# SCH_SIT210_Task_7_3D_PCB_2022-06-06.net
KiCad netlist of a schematic drawn in EasyEDA
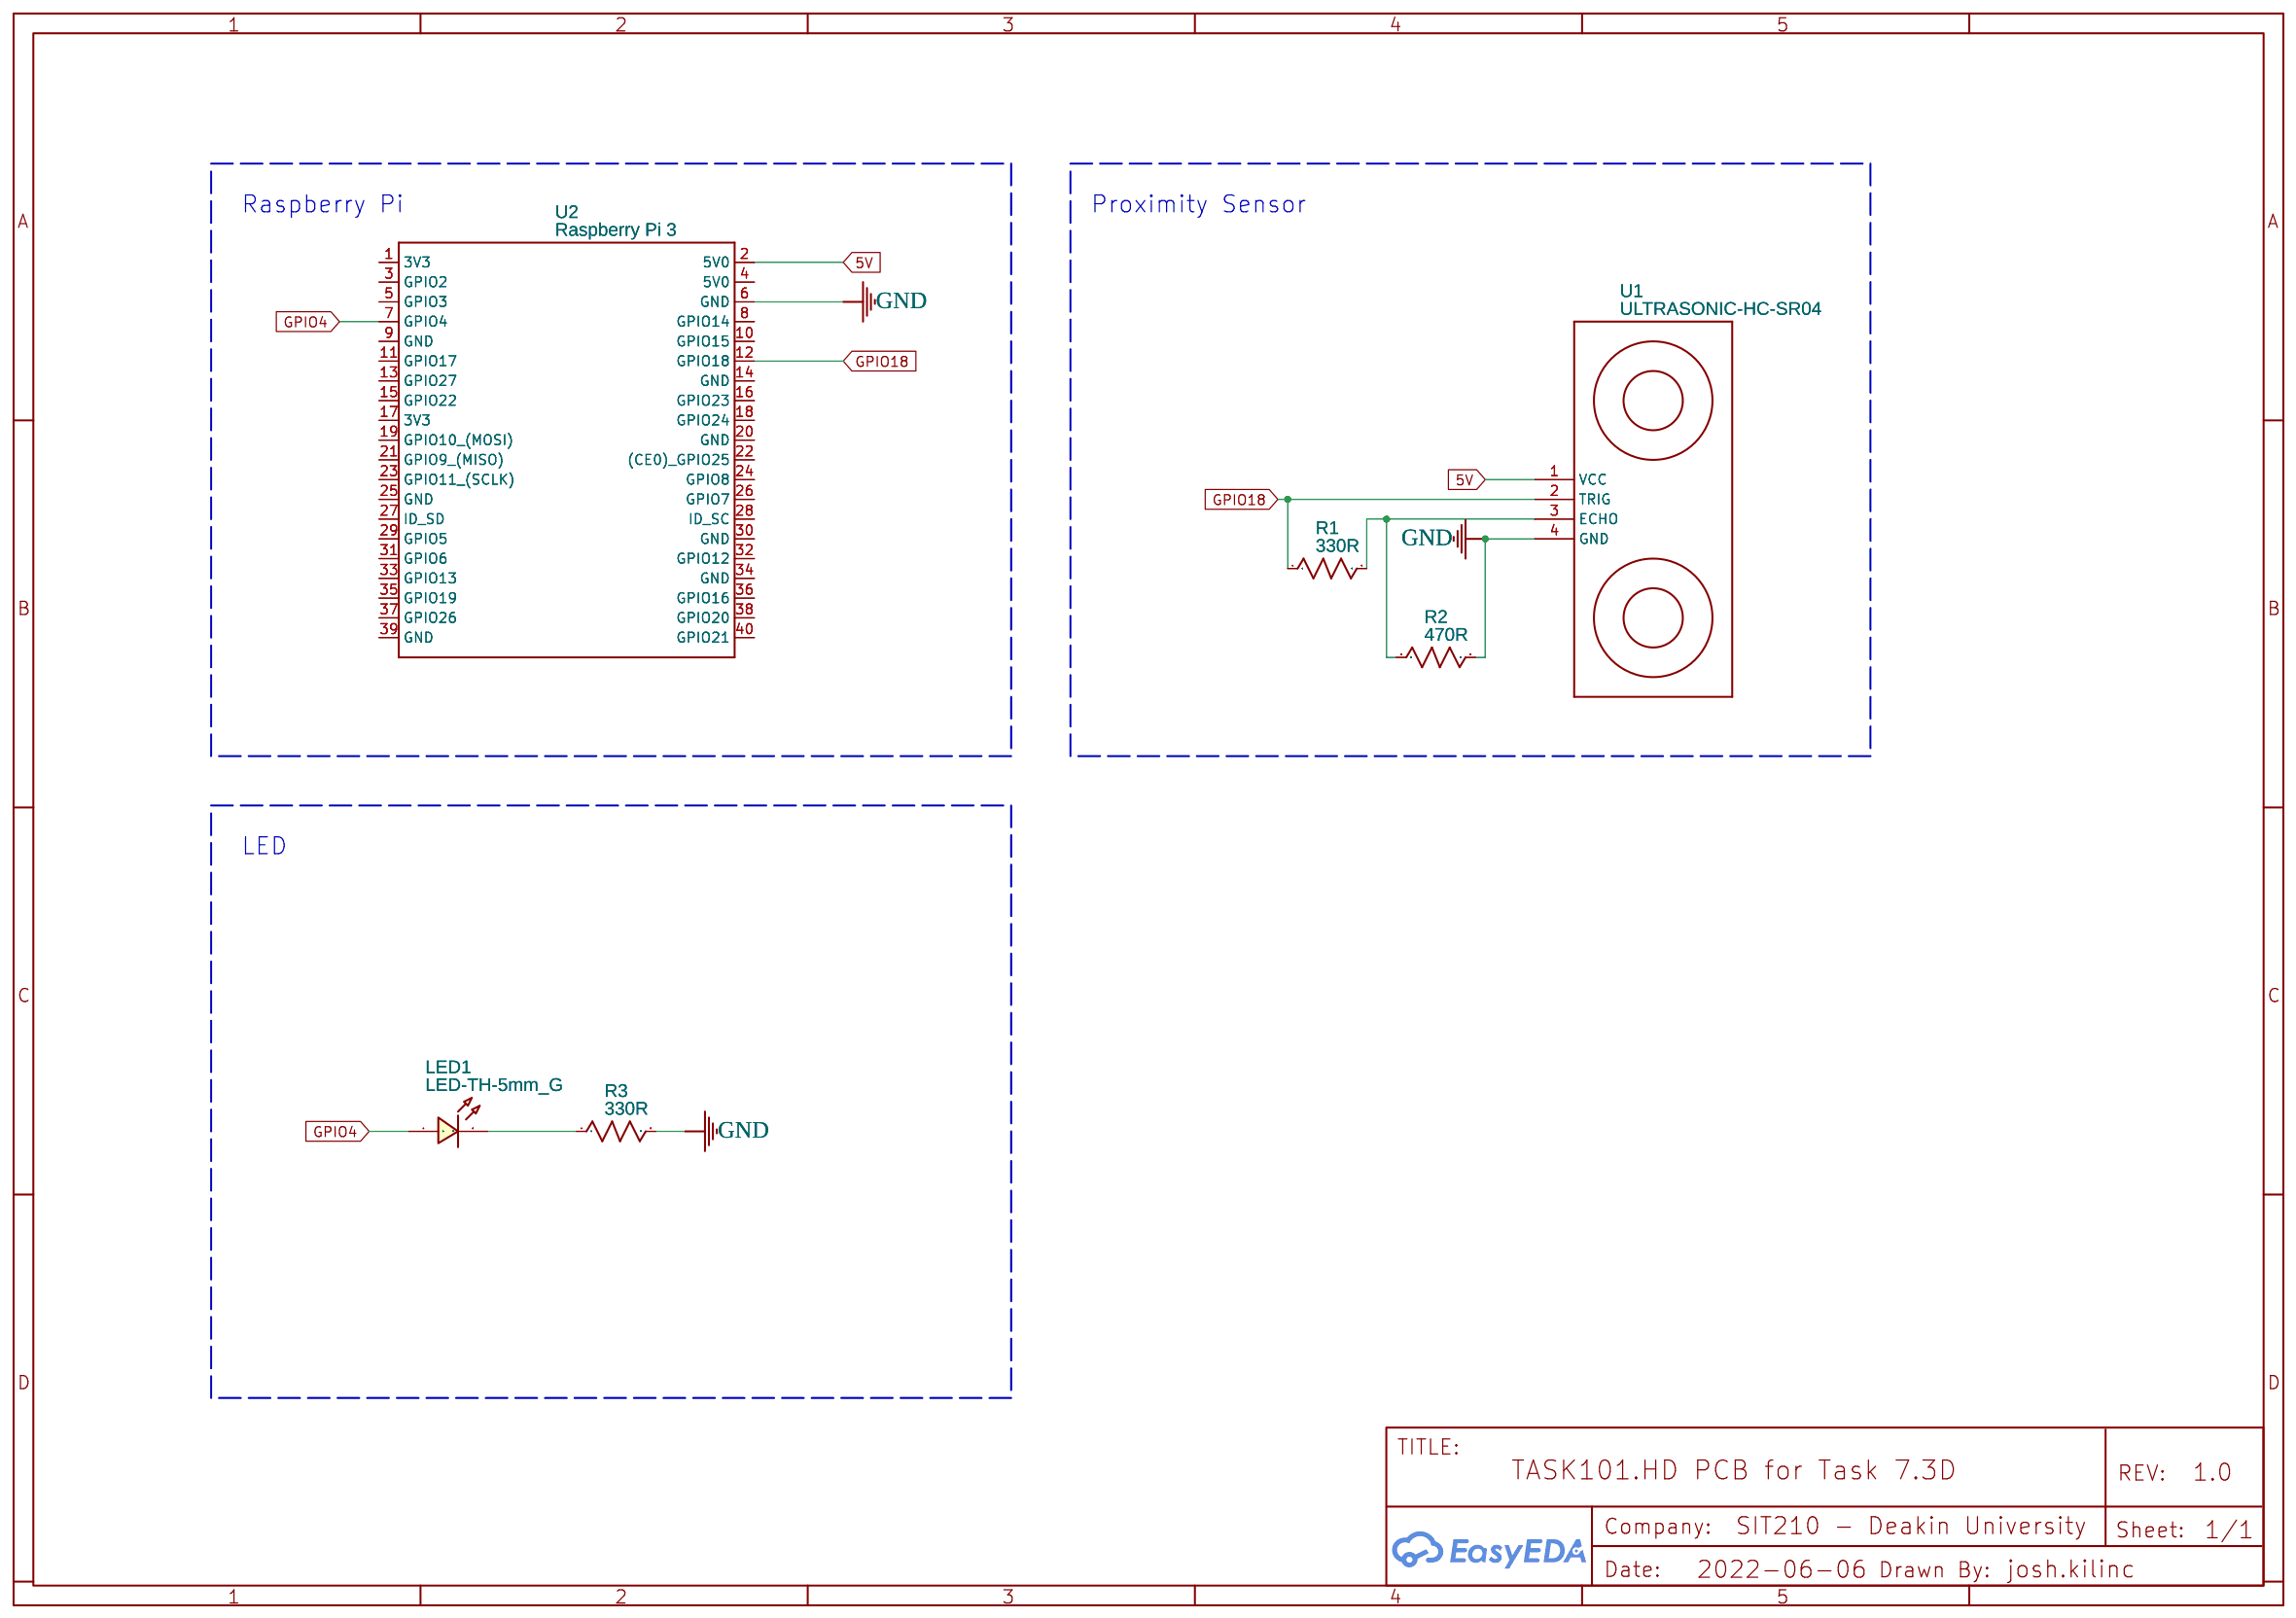
[diagram p0: schematic sheet]

(export (version "E")
  (design (tool "Eeschema 10.0.6"))
  (components
    (comp (ref "LED1")
      (value "LED-TH-5mm_G")
      (fields
        (field (name "BOM_Manufacturer Part") "333-2SYGD/S530-E2")
        (field (name "BOM_Supplier Part") "C88163")
      )
      (libsource (lib "") (part "LED-TH-5mm_G"))
    )
    (comp (ref "R1") (value "330R") (libsource (lib "") (part "R_0603_US")))
    (comp (ref "R2") (value "470R") (libsource (lib "") (part "R_0603_US")))
    (comp (ref "R3") (value "330R") (libsource (lib "") (part "R_0603_US")))
    (comp (ref "U1") (value "ULTRASONIC-HC-SR04") (libsource (lib "") (part "ULTRASONIC-HC-SR04")))
    (comp (ref "U2")
      (value "Raspberry Pi 3")
      (fields (field (name "BOM_Supplier Part") "RaspberryPi 3"))
      (libsource (lib "") (part "Raspberry Pi 3"))
    )
  )
  (nets
    (net (code "1") (name "5V") (class "Default")
      (node (ref "U1") (pin "1") (pinfunction "VCC_1") (pintype "passive"))
      (node (ref "U2") (pin "2") (pinfunction "5V0_2") (pintype "unspecified"))
    )
    (net (code "2") (name "GND") (class "Default")
      (node (ref "R2") (pin "2") (pinfunction "2_2") (pintype "unspecified"))
      (node (ref "R3") (pin "2") (pinfunction "2_2") (pintype "unspecified"))
      (node (ref "U1") (pin "4") (pinfunction "GND_4") (pintype "passive"))
      (node (ref "U2") (pin "6") (pinfunction "GND_6") (pintype "unspecified"))
    )
    (net (code "3") (name "GPIO4") (class "Default")
      (node (ref "LED1") (pin "1") (pinfunction "1_1") (pintype "unspecified"))
      (node (ref "U2") (pin "7") (pinfunction "GPIO4_7") (pintype "unspecified"))
    )
    (net (code "4") (name "GPIO18") (class "Default")
      (node (ref "R1") (pin "1") (pinfunction "1_1") (pintype "unspecified"))
      (node (ref "U1") (pin "2") (pinfunction "TRIG_2") (pintype "input"))
      (node (ref "U2") (pin "12") (pinfunction "GPIO18_12") (pintype "unspecified"))
    )
    (net (code "5") (name "Net-(LED1-Pad2)") (class "Default")
      (node (ref "LED1") (pin "2") (pinfunction "2_2") (pintype "unspecified"))
      (node (ref "R3") (pin "1") (pinfunction "1_1") (pintype "unspecified"))
    )
    (net (code "6") (name "Net-(U1-ECHO)") (class "Default")
      (node (ref "R1") (pin "2") (pinfunction "2_2") (pintype "unspecified"))
      (node (ref "R2") (pin "1") (pinfunction "1_1") (pintype "unspecified"))
      (node (ref "U1") (pin "3") (pinfunction "ECHO_3") (pintype "output"))
    )
    (net (code "7") (name "unconnected-(U2-(CE0)_GPIO25-Pad22)") (class "Default")
      (node (ref "U2") (pin "22") (pinfunction "(CE0)_GPIO25_22") (pintype "unspecified"))
    )
    (net (code "8") (name "unconnected-(U2-3V3-Pad1)") (class "Default")
      (node (ref "U2") (pin "1") (pinfunction "3V3_1") (pintype "unspecified"))
    )
    (net (code "9") (name "unconnected-(U2-3V3-Pad17)") (class "Default")
      (node (ref "U2") (pin "17") (pinfunction "3V3_17") (pintype "unspecified"))
    )
    (net (code "10") (name "unconnected-(U2-5V0-Pad4)") (class "Default")
      (node (ref "U2") (pin "4") (pinfunction "5V0_4") (pintype "unspecified"))
    )
    (net (code "11") (name "unconnected-(U2-GND-Pad9)") (class "Default")
      (node (ref "U2") (pin "9") (pinfunction "GND_9") (pintype "unspecified"))
    )
    (net (code "12") (name "unconnected-(U2-GND-Pad14)") (class "Default")
      (node (ref "U2") (pin "14") (pinfunction "GND_14") (pintype "unspecified"))
    )
    (net (code "13") (name "unconnected-(U2-GND-Pad20)") (class "Default")
      (node (ref "U2") (pin "20") (pinfunction "GND_20") (pintype "unspecified"))
    )
    (net (code "14") (name "unconnected-(U2-GND-Pad25)") (class "Default")
      (node (ref "U2") (pin "25") (pinfunction "GND_25") (pintype "unspecified"))
    )
    (net (code "15") (name "unconnected-(U2-GND-Pad30)") (class "Default")
      (node (ref "U2") (pin "30") (pinfunction "GND_30") (pintype "unspecified"))
    )
    (net (code "16") (name "unconnected-(U2-GND-Pad34)") (class "Default")
      (node (ref "U2") (pin "34") (pinfunction "GND_34") (pintype "unspecified"))
    )
    (net (code "17") (name "unconnected-(U2-GND-Pad39)") (class "Default")
      (node (ref "U2") (pin "39") (pinfunction "GND_39") (pintype "unspecified"))
    )
    (net (code "18") (name "unconnected-(U2-GPIO2-Pad3)") (class "Default")
      (node (ref "U2") (pin "3") (pinfunction "GPIO2_3") (pintype "unspecified"))
    )
    (net (code "19") (name "unconnected-(U2-GPIO3-Pad5)") (class "Default")
      (node (ref "U2") (pin "5") (pinfunction "GPIO3_5") (pintype "unspecified"))
    )
    (net (code "20") (name "unconnected-(U2-GPIO5-Pad29)") (class "Default")
      (node (ref "U2") (pin "29") (pinfunction "GPIO5_29") (pintype "unspecified"))
    )
    (net (code "21") (name "unconnected-(U2-GPIO6-Pad31)") (class "Default")
      (node (ref "U2") (pin "31") (pinfunction "GPIO6_31") (pintype "unspecified"))
    )
    (net (code "22") (name "unconnected-(U2-GPIO7-Pad26)") (class "Default")
      (node (ref "U2") (pin "26") (pinfunction "GPIO7_26") (pintype "unspecified"))
    )
    (net (code "23") (name "unconnected-(U2-GPIO8-Pad24)") (class "Default")
      (node (ref "U2") (pin "24") (pinfunction "GPIO8_24") (pintype "unspecified"))
    )
    (net (code "24") (name "unconnected-(U2-GPIO9_(MISO)-Pad21)") (class "Default")
      (node (ref "U2") (pin "21") (pinfunction "GPIO9_(MISO)_21") (pintype "unspecified"))
    )
    (net (code "25") (name "unconnected-(U2-GPIO10_(MOSI)-Pad19)") (class "Default")
      (node (ref "U2") (pin "19") (pinfunction "GPIO10_(MOSI)_19") (pintype "unspecified"))
    )
    (net (code "26") (name "unconnected-(U2-GPIO11_(SCLK)-Pad23)") (class "Default")
      (node (ref "U2") (pin "23") (pinfunction "GPIO11_(SCLK)_23") (pintype "unspecified"))
    )
    (net (code "27") (name "unconnected-(U2-GPIO12-Pad32)") (class "Default")
      (node (ref "U2") (pin "32") (pinfunction "GPIO12_32") (pintype "unspecified"))
    )
    (net (code "28") (name "unconnected-(U2-GPIO13-Pad33)") (class "Default")
      (node (ref "U2") (pin "33") (pinfunction "GPIO13_33") (pintype "unspecified"))
    )
    (net (code "29") (name "unconnected-(U2-GPIO14-Pad8)") (class "Default")
      (node (ref "U2") (pin "8") (pinfunction "GPIO14_8") (pintype "unspecified"))
    )
    (net (code "30") (name "unconnected-(U2-GPIO15-Pad10)") (class "Default")
      (node (ref "U2") (pin "10") (pinfunction "GPIO15_10") (pintype "unspecified"))
    )
    (net (code "31") (name "unconnected-(U2-GPIO16-Pad36)") (class "Default")
      (node (ref "U2") (pin "36") (pinfunction "GPIO16_36") (pintype "unspecified"))
    )
    (net (code "32") (name "unconnected-(U2-GPIO17-Pad11)") (class "Default")
      (node (ref "U2") (pin "11") (pinfunction "GPIO17_11") (pintype "unspecified"))
    )
    (net (code "33") (name "unconnected-(U2-GPIO19-Pad35)") (class "Default")
      (node (ref "U2") (pin "35") (pinfunction "GPIO19_35") (pintype "unspecified"))
    )
    (net (code "34") (name "unconnected-(U2-GPIO20-Pad38)") (class "Default")
      (node (ref "U2") (pin "38") (pinfunction "GPIO20_38") (pintype "unspecified"))
    )
    (net (code "35") (name "unconnected-(U2-GPIO21-Pad40)") (class "Default")
      (node (ref "U2") (pin "40") (pinfunction "GPIO21_40") (pintype "unspecified"))
    )
    (net (code "36") (name "unconnected-(U2-GPIO22-Pad15)") (class "Default")
      (node (ref "U2") (pin "15") (pinfunction "GPIO22_15") (pintype "unspecified"))
    )
    (net (code "37") (name "unconnected-(U2-GPIO23-Pad16)") (class "Default")
      (node (ref "U2") (pin "16") (pinfunction "GPIO23_16") (pintype "unspecified"))
    )
    (net (code "38") (name "unconnected-(U2-GPIO24-Pad18)") (class "Default")
      (node (ref "U2") (pin "18") (pinfunction "GPIO24_18") (pintype "unspecified"))
    )
    (net (code "39") (name "unconnected-(U2-GPIO26-Pad37)") (class "Default")
      (node (ref "U2") (pin "37") (pinfunction "GPIO26_37") (pintype "unspecified"))
    )
    (net (code "40") (name "unconnected-(U2-GPIO27-Pad13)") (class "Default")
      (node (ref "U2") (pin "13") (pinfunction "GPIO27_13") (pintype "unspecified"))
    )
    (net (code "41") (name "unconnected-(U2-ID_SC-Pad28)") (class "Default")
      (node (ref "U2") (pin "28") (pinfunction "ID_SC_28") (pintype "unspecified"))
    )
    (net (code "42") (name "unconnected-(U2-ID_SD-Pad27)") (class "Default")
      (node (ref "U2") (pin "27") (pinfunction "ID_SD_27") (pintype "unspecified"))
    )
  )
)
